# Sheet1.net
KiCad netlist of a schematic drawn in Altium Designer
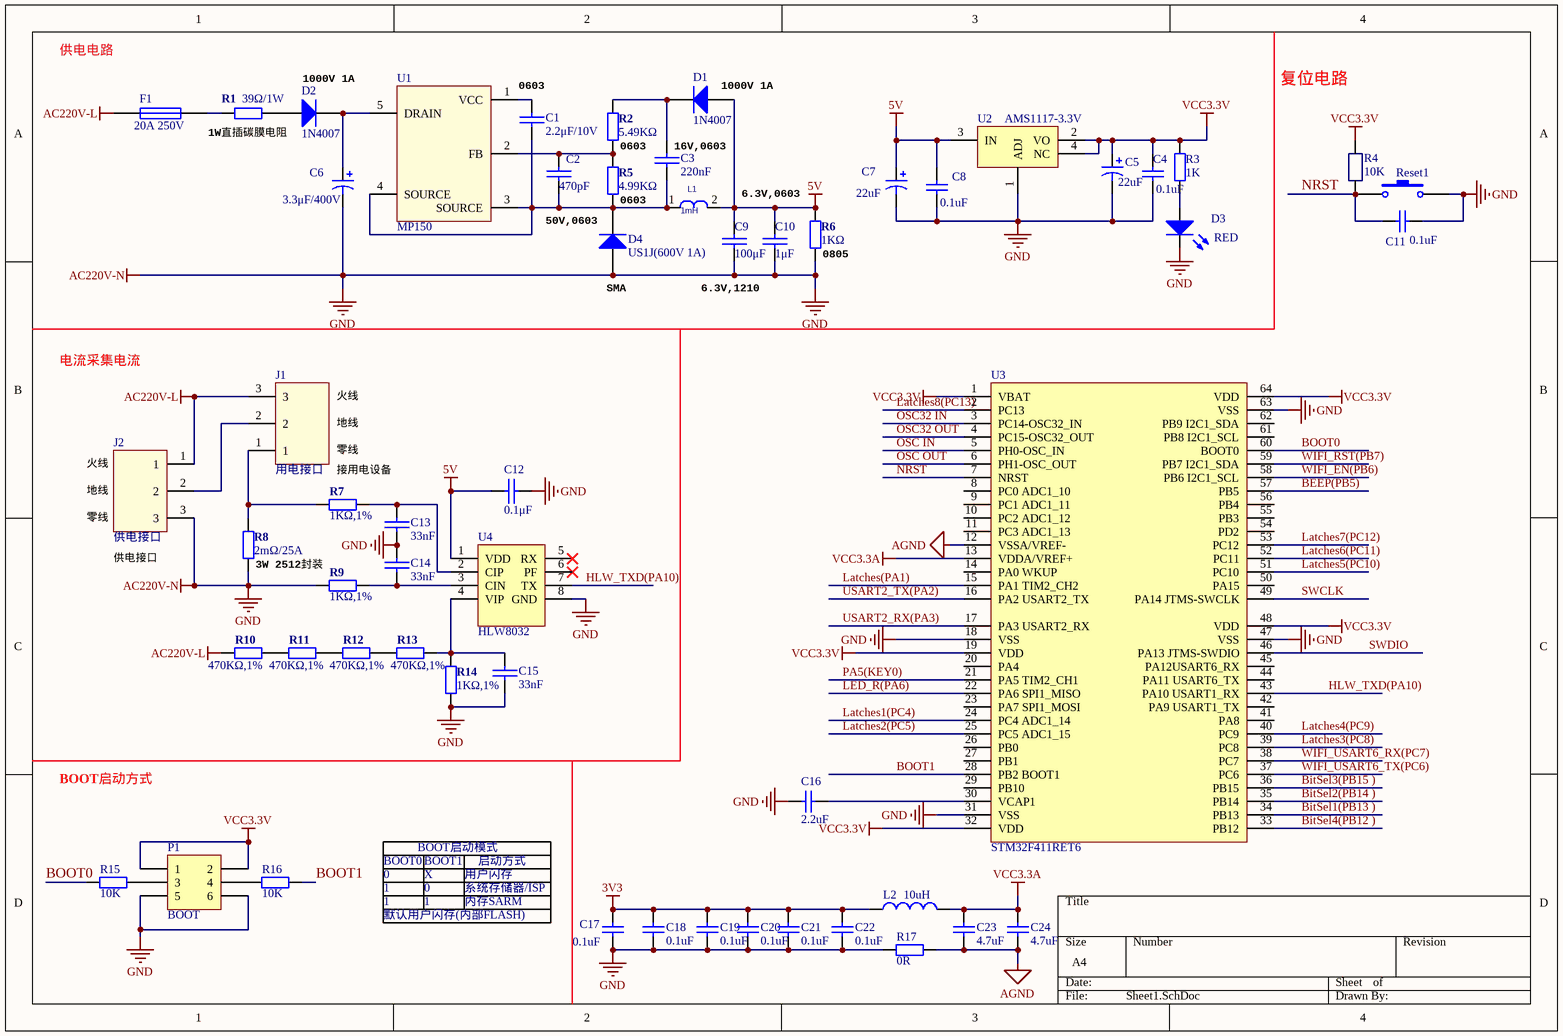
[diagram p0: Sheet1.SchDoc]

(export (version "E")
  (design (tool "Eeschema 10.0.6"))
  (components
    (comp (ref "C1")
      (value "2.2μF/10V")
      (footprint "LC-0603_C(2.2UF/10V)")
      (description "贴片电容")
      (libsource (lib "原理图库") (part "CAP"))
    )
    (comp (ref "C2")
      (value "470pF")
      (footprint "LC-0603_C(普通电容)")
      (description "贴片电容")
      (libsource (lib "原理图库") (part "CAP"))
    )
    (comp (ref "C3")
      (value "220nF")
      (footprint "LC-0603_C(普通电容)")
      (description "贴片电容")
      (libsource (lib "原理图库") (part "CAP"))
    )
    (comp (ref "C4")
      (value "0.1uF")
      (footprint "LC-0603_C(普通电容)")
      (description "贴片电容")
      (libsource (lib "Schlib1") (part "CAP"))
    )
    (comp (ref "C5")
      (value "22uF")
      (footprint "钽电容0603（25v）")
      (description "钽电容")
      (libsource (lib "Schlib1") (part "Cap Pol2"))
    )
    (comp (ref "C6")
      (value "3.3μF/400V")
      (footprint "直插电解电容 - duplicate")
      (description "直插电解电容")
      (libsource (lib "Miscellaneous Devices") (part "Cap Pol1"))
    )
    (comp (ref "C7")
      (value "22uF")
      (footprint "钽电容0603（25v）")
      (description "钽电容、")
      (libsource (lib "Schlib1") (part "Cap Pol2"))
    )
    (comp (ref "C8")
      (value "0.1uF")
      (footprint "LC-0603_C(普通电容)")
      (description "贴片电容")
      (libsource (lib "Schlib1") (part "CAP"))
    )
    (comp (ref "C9")
      (value "100μF")
      (footprint "LC-1210_C大电容")
      (description "贴片电容")
      (libsource (lib "原理图库") (part "CAP"))
    )
    (comp (ref "C10")
      (value "1μF")
      (footprint "LC-0603_C(普通电容)")
      (description "贴片电容")
      (libsource (lib "原理图库") (part "CAP"))
    )
    (comp (ref "C11")
      (value "0.1uF")
      (footprint "LC-0603_C(普通电容)")
      (description "贴片电容")
      (fields (field (name "PUBLISHER") "Altium Limited"))
      (libsource (lib "Miscellaneous Devices") (part "Cap Semi"))
    )
    (comp (ref "C12")
      (value "0.1μF")
      (footprint "LC-0603_C(普通电容)")
      (description "贴片电容")
      (libsource (lib "原理图库") (part "CAP"))
    )
    (comp (ref "C13")
      (value "33nF")
      (footprint "LC-0805_C")
      (description "贴片电容")
      (libsource (lib "原理图库") (part "CAP"))
    )
    (comp (ref "C14")
      (value "33nF")
      (footprint "LC-0805_C")
      (description "贴片电容")
      (libsource (lib "原理图库") (part "CAP"))
    )
    (comp (ref "C15")
      (value "33nF")
      (footprint "LC-0805_C")
      (description "贴片电容")
      (libsource (lib "原理图库") (part "CAP"))
    )
    (comp (ref "C16")
      (value "2.2uF")
      (footprint "PcbLib1:LC-0603_C(普通电容)")
      (description "贴片电容")
      (libsource (lib "Schlib1") (part "CAP"))
    )
    (comp (ref "C17")
      (value "0.1uF")
      (footprint "PcbLib1:LC-0603_C(普通电容)")
      (description "贴片电容")
      (libsource (lib "Schlib1") (part "CAP"))
    )
    (comp (ref "C18")
      (value "0.1uF")
      (footprint "LC-0603_C(普通电容)")
      (description "贴片电容")
      (libsource (lib "Schlib1") (part "CAP"))
    )
    (comp (ref "C19")
      (value "0.1uF")
      (footprint "PcbLib1:LC-0603_C(普通电容)")
      (description "贴片电容")
      (libsource (lib "Schlib1") (part "CAP"))
    )
    (comp (ref "C20")
      (value "0.1uF")
      (footprint "PcbLib1:LC-0603_C(普通电容)")
      (description "贴片电容")
      (libsource (lib "Schlib1") (part "CAP"))
    )
    (comp (ref "C21")
      (value "0.1uF")
      (footprint "PcbLib1:LC-0603_C(普通电容)")
      (description "贴片电容")
      (libsource (lib "Schlib1") (part "CAP"))
    )
    (comp (ref "C22")
      (value "0.1uF")
      (footprint "PcbLib1:LC-0603_C(普通电容)")
      (description "贴片电容")
      (libsource (lib "Schlib1") (part "CAP"))
    )
    (comp (ref "C23")
      (value "4.7uF")
      (footprint "PcbLib1:LC-0603_C(普通电容)")
      (description "贴片电容")
      (libsource (lib "Schlib1") (part "CAP"))
    )
    (comp (ref "C24")
      (value "4.7uF")
      (footprint "PcbLib1:LC-0603_C(普通电容)")
      (description "贴片电容")
      (libsource (lib "Schlib1") (part "CAP"))
    )
    (comp (ref "D1")
      (value "1N4007")
      (footprint "1N4007")
      (description "贴片二极管")
      (libsource (lib "Miscellaneous Devices") (part "Diode 1N5408"))
    )
    (comp (ref "D2")
      (value "1N4007")
      (footprint "1N4007")
      (description "贴片二极管")
      (libsource (lib "Miscellaneous Devices") (part "Diode 1N5408"))
    )
    (comp (ref "D3")
      (value "RED")
      (footprint "LED0603")
      (description "发光二极管0603")
      (libsource (lib "Schlib1") (part "LED1"))
    )
    (comp (ref "D4")
      (value "US1J(600V 1A)")
      (footprint "US1J二极管LC-SMA(DO-214AC)_S1")
      (description "贴片二极管")
      (fields (field (name "PUBLISHER") "Altium Limited"))
      (libsource (lib "Miscellaneous Devices") (part "Diode 1N5408"))
    )
    (comp (ref "F1")
      (value "20A 250V")
      (footprint "FUSE_BASE")
      (description "Fuse")
      (libsource (lib "Miscellaneous Devices") (part "Fuse 1"))
    )
    (comp (ref "J1")
      (value "用电接口")
      (footprint "3.81-3P(接线端子)输出")
      (description "直插接线端子")
      (libsource (lib "") (part "Port-3P_1"))
    )
    (comp (ref "J2")
      (value "供电接口")
      (footprint "3.81-3P(接线端子)输入")
      (description "直插接线端子")
      (libsource (lib "HLW8012-Demo") (part "Port-3P"))
    )
    (comp (ref "L1")
      (value "1mH")
      (footprint "L-10X14(电感)")
      (description "直插绕线电感")
      (libsource (lib "*") (part "IND_8"))
    )
    (comp (ref "L2")
      (value "10uH")
      (footprint "PcbLib1:电感(L0603)")
      (description "Inductor")
      (libsource (lib "Schlib1") (part "Inductor"))
    )
    (comp (ref "P1")
      (value "BOOT")
      (footprint "Header2*3 2.54mm")
      (description "Header, 3-Pin, 杜邦线2.54")
      (fields (field (name "PUBLISHER") "Altium Limited"))
      (libsource (lib "阿波罗STM32F4&F7底板封装库") (part "Header 3X2"))
    )
    (comp (ref "R1")
      (value "39Ω/1W")
      (footprint "炭膜电阻")
      (description "贴片电阻")
      (libsource (lib "") (part "电阻_3"))
    )
    (comp (ref "R2")
      (value "5.49KΩ")
      (footprint "LC-0603_R(电阻)")
      (description "贴片电阻")
      (libsource (lib "") (part "电阻_2"))
    )
    (comp (ref "R3")
      (value "1K")
      (footprint "LC-0603_R(电阻)")
      (description "贴片电阻")
      (fields (field (name "Comment") "10k") (field (name "PUBLISHER") "Altium Limited"))
      (libsource (lib "Miscellaneous Devices") (part "Res2"))
    )
    (comp (ref "R4")
      (value "10K")
      (footprint "LC-0603_R(电阻)")
      (description "贴片电阻")
      (libsource (lib "PCB") (part "RES"))
    )
    (comp (ref "R5")
      (value "4.99KΩ")
      (footprint "LC-0603_R(电阻)")
      (description "贴片电阻")
      (libsource (lib "") (part "电阻_2"))
    )
    (comp (ref "R6")
      (value "1KΩ")
      (footprint "LC-0805_R")
      (description "贴片电阻")
      (libsource (lib "") (part "电阻_2"))
    )
    (comp (ref "R7")
      (value "1KΩ,1%")
      (footprint "LC-0805_R")
      (description "贴片电阻")
      (libsource (lib "") (part "电阻_1"))
    )
    (comp (ref "R8")
      (value "2mΩ/25A")
      (footprint "R2512猛铜电阻")
      (description "贴片电阻")
      (libsource (lib "FourAxis") (part "电阻"))
    )
    (comp (ref "R9")
      (value "1KΩ,1%")
      (footprint "LC-0805_R")
      (description "贴片电阻")
      (libsource (lib "") (part "电阻_1"))
    )
    (comp (ref "R10")
      (value "470KΩ,1%")
      (footprint "LC-0805_R")
      (description "贴片电阻")
      (libsource (lib "") (part "电阻_1"))
    )
    (comp (ref "R11")
      (value "470KΩ,1%")
      (footprint "LC-0805_R")
      (description "贴片电阻")
      (libsource (lib "") (part "电阻_1"))
    )
    (comp (ref "R12")
      (value "470KΩ,1%")
      (footprint "LC-0805_R")
      (description "贴片电阻")
      (libsource (lib "") (part "电阻_1"))
    )
    (comp (ref "R13")
      (value "470KΩ,1%")
      (footprint "LC-0805_R")
      (description "贴片电阻")
      (libsource (lib "") (part "电阻_1"))
    )
    (comp (ref "R14")
      (value "1KΩ,1%")
      (footprint "LC-0805_R")
      (description "贴片电阻")
      (libsource (lib "FourAxis") (part "电阻"))
    )
    (comp (ref "R15")
      (value "10K")
      (footprint "LC-0603_R(电阻)")
      (description "贴片电阻")
      (fields (field (name "Comment") "10k") (field (name "PUBLISHER") "Altium Limited"))
      (libsource (lib "") (part "Res2_1"))
    )
    (comp (ref "R16")
      (value "10K")
      (footprint "LC-0603_R(电阻)")
      (description "贴片电阻")
      (fields (field (name "Comment") "10k") (field (name "PUBLISHER") "Altium Limited"))
      (libsource (lib "") (part "Res2_1"))
    )
    (comp (ref "R17")
      (value "0R")
      (footprint "LC-0603_R(电阻)")
      (description "贴片电阻")
      (fields (field (name "Comment") "10k") (field (name "PUBLISHER") "Altium Limited"))
      (libsource (lib "") (part "Res2_1"))
    )
    (comp (ref "Reset1")
      (value "SW-PB")
      (footprint "key")
      (description "轻触开关 3*6*2.5mm 白头")
      (fields (field (name "PUBLISHER") "Altium Limited"))
      (libsource (lib "Miscellaneous Devices") (part "SW-PB"))
    )
    (comp (ref "U1")
      (value "MP150")
      (footprint "MP150(LC-SOT-23-5)")
      (description "IC")
      (libsource (lib "HLW8012-Demo") (part "MP150"))
    )
    (comp (ref "U2")
      (value "AMS1117-3.3V")
      (footprint "SOT-223(ASM117-3.3)")
      (description "稳压芯片转3V3")
      (libsource (lib "Schlib1") (part "AMS1117-3.3V"))
    )
    (comp (ref "U3")
      (value "STM32F411RET6")
      (footprint "MCU-LQFP64")
      (description "MCU")
      (libsource (lib "Schlib1") (part "STM32F411"))
    )
    (comp (ref "U4")
      (value "HLW8032")
      (footprint "(HLW8032)LC-SOP-8_150mil")
      (description "电量计芯片")
      (libsource (lib "Schlib1") (part "HLW8032"))
    )
  )
  (nets
    (net (code "1") (name "/BEEP(PB5)") (class "Default")
      (node (ref "U3") (pin "57") (pinfunction "PB5_57") (pintype "passive"))
    )
    (net (code "2") (name "/BOOT0") (class "Default")
      (node (ref "R15") (pin "2") (pinfunction "2_2") (pintype "passive"))
      (node (ref "U3") (pin "60") (pinfunction "BOOT0_60") (pintype "passive"))
    )
    (net (code "3") (name "/BOOT1") (class "Default")
      (node (ref "R16") (pin "1") (pinfunction "1_1") (pintype "passive"))
      (node (ref "U3") (pin "28") (pinfunction "PB2_BOOT1_28") (pintype "passive"))
    )
    (net (code "4") (name "/BitSel1(PB13 )") (class "Default")
      (node (ref "U3") (pin "34") (pinfunction "PB13_34") (pintype "passive"))
    )
    (net (code "5") (name "/BitSel2(PB14 )") (class "Default")
      (node (ref "U3") (pin "35") (pinfunction "PB14_35") (pintype "passive"))
    )
    (net (code "6") (name "/BitSel3(PB15 )") (class "Default")
      (node (ref "U3") (pin "36") (pinfunction "PB15_36") (pintype "passive"))
    )
    (net (code "7") (name "/BitSel4(PB12 )") (class "Default")
      (node (ref "U3") (pin "33") (pinfunction "PB12_33") (pintype "passive"))
    )
    (net (code "8") (name "/HLW_TXD(PA10)") (class "Default")
      (node (ref "U3") (pin "43") (pinfunction "PA10_USART1_RX_43") (pintype "passive"))
      (node (ref "U4") (pin "7") (pinfunction "TX_7") (pintype "passive"))
    )
    (net (code "9") (name "/LED_R(PA6)") (class "Default")
      (node (ref "U3") (pin "22") (pinfunction "PA6_SPI1_MISO_22") (pintype "passive"))
    )
    (net (code "10") (name "/Latches(PA1)") (class "Default")
      (node (ref "U3") (pin "15") (pinfunction "PA1_TIM2_CH2_15") (pintype "passive"))
    )
    (net (code "11") (name "/Latches1(PC4)") (class "Default")
      (node (ref "U3") (pin "24") (pinfunction "PC4_ADC1_14_24") (pintype "passive"))
    )
    (net (code "12") (name "/Latches2(PC5)") (class "Default")
      (node (ref "U3") (pin "25") (pinfunction "PC5_ADC1_15_25") (pintype "passive"))
    )
    (net (code "13") (name "/Latches3(PC8)") (class "Default")
      (node (ref "U3") (pin "39") (pinfunction "PC8_39") (pintype "passive"))
    )
    (net (code "14") (name "/Latches4(PC9)") (class "Default")
      (node (ref "U3") (pin "40") (pinfunction "PC9_40") (pintype "passive"))
    )
    (net (code "15") (name "/Latches5(PC10)") (class "Default")
      (node (ref "U3") (pin "51") (pinfunction "PC10_51") (pintype "passive"))
    )
    (net (code "16") (name "/Latches6(PC11)") (class "Default")
      (node (ref "U3") (pin "52") (pinfunction "PC11_52") (pintype "passive"))
    )
    (net (code "17") (name "/Latches7(PC12)") (class "Default")
      (node (ref "U3") (pin "53") (pinfunction "PC12_53") (pintype "passive"))
    )
    (net (code "18") (name "/Latches8(PC13)") (class "Default")
      (node (ref "U3") (pin "2") (pinfunction "PC13_2") (pintype "passive"))
    )
    (net (code "19") (name "/NRST") (class "Default")
      (node (ref "C11") (pin "2") (pinfunction "2_2") (pintype "passive"))
      (node (ref "R4") (pin "1") (pinfunction "1_1") (pintype "passive"))
      (node (ref "Reset1") (pin "1") (pinfunction "1_1") (pintype "passive"))
      (node (ref "U3") (pin "7") (pinfunction "NRST_7") (pintype "passive"))
    )
    (net (code "20") (name "/OSC IN") (class "Default")
      (node (ref "U3") (pin "5") (pinfunction "PH0-OSC_IN_5") (pintype "passive"))
    )
    (net (code "21") (name "/OSC OUT") (class "Default")
      (node (ref "U3") (pin "6") (pinfunction "PH1-OSC_OUT_6") (pintype "passive"))
    )
    (net (code "22") (name "/OSC32 IN") (class "Default")
      (node (ref "U3") (pin "3") (pinfunction "PC14-OSC32_IN_3") (pintype "passive"))
    )
    (net (code "23") (name "/OSC32 OUT") (class "Default")
      (node (ref "U3") (pin "4") (pinfunction "PC15-OSC32_OUT_4") (pintype "passive"))
    )
    (net (code "24") (name "/PA5(KEY0)") (class "Default")
      (node (ref "U3") (pin "21") (pinfunction "PA5_TIM2_CH1_21") (pintype "passive"))
    )
    (net (code "25") (name "/SWCLK") (class "Default")
      (node (ref "U3") (pin "49") (pinfunction "PA14_JTMS-SWCLK_49") (pintype "passive"))
    )
    (net (code "26") (name "/SWDIO") (class "Default")
      (node (ref "U3") (pin "46") (pinfunction "PA13_JTMS-SWDIO_46") (pintype "passive"))
    )
    (net (code "27") (name "/USART2_RX(PA3)") (class "Default")
      (node (ref "U3") (pin "17") (pinfunction "PA3_USART2_RX_17") (pintype "passive"))
    )
    (net (code "28") (name "/USART2_TX(PA2)") (class "Default")
      (node (ref "U3") (pin "16") (pinfunction "PA2_USART2_TX_16") (pintype "passive"))
    )
    (net (code "29") (name "/WIFI_EN(PB6)") (class "Default")
      (node (ref "U3") (pin "58") (pinfunction "PB6_I2C1_SCL_58") (pintype "passive"))
    )
    (net (code "30") (name "/WIFI_RST(PB7)") (class "Default")
      (node (ref "U3") (pin "59") (pinfunction "PB7_I2C1_SDA_59") (pintype "passive"))
    )
    (net (code "31") (name "/WIFI_USART6_RX(PC7)") (class "Default")
      (node (ref "U3") (pin "38") (pinfunction "PC7_38") (pintype "passive"))
    )
    (net (code "32") (name "/WIFI_USART6_TX(PC6)") (class "Default")
      (node (ref "U3") (pin "37") (pinfunction "PC6_37") (pintype "passive"))
    )
    (net (code "33") (name "3V3") (class "Default")
      (node (ref "C17") (pin "2") (pinfunction "2_2") (pintype "passive"))
      (node (ref "C18") (pin "2") (pinfunction "2_2") (pintype "passive"))
      (node (ref "C19") (pin "2") (pinfunction "2_2") (pintype "passive"))
      (node (ref "C20") (pin "1") (pinfunction "1_1") (pintype "passive"))
      (node (ref "C21") (pin "1") (pinfunction "1_1") (pintype "passive"))
      (node (ref "C22") (pin "1") (pinfunction "1_1") (pintype "passive"))
      (node (ref "L2") (pin "1") (pinfunction "1_1") (pintype "passive"))
    )
    (net (code "34") (name "5V") (class "Default")
      (node (ref "C10") (pin "2") (pinfunction "2_2") (pintype "passive"))
      (node (ref "C12") (pin "1") (pinfunction "1_1") (pintype "passive"))
      (node (ref "C7") (pin "1") (pinfunction "1_1") (pintype "passive"))
      (node (ref "C8") (pin "2") (pinfunction "2_2") (pintype "passive"))
      (node (ref "C9") (pin "2") (pinfunction "2_2") (pintype "passive"))
      (node (ref "D1") (pin "1") (pinfunction "A_1") (pintype "passive"))
      (node (ref "L1") (pin "2") (pinfunction "2_2") (pintype "passive"))
      (node (ref "R6") (pin "2") (pinfunction "2_2") (pintype "passive"))
      (node (ref "U2") (pin "3") (pinfunction "IN_3") (pintype "passive"))
      (node (ref "U4") (pin "1") (pinfunction "VDD_1") (pintype "passive"))
    )
    (net (code "35") (name "AC220V-L") (class "Default")
      (node (ref "F1") (pin "2") (pinfunction "2_2") (pintype "passive"))
      (node (ref "J1") (pin "3") (pinfunction "3_3") (pintype "passive"))
      (node (ref "J2") (pin "1") (pinfunction "1_1") (pintype "passive"))
      (node (ref "R10") (pin "2") (pinfunction "2_2") (pintype "passive"))
    )
    (net (code "36") (name "AC220V-N") (class "Default")
      (node (ref "C10") (pin "1") (pinfunction "1_1") (pintype "passive"))
      (node (ref "C11") (pin "1") (pinfunction "1_1") (pintype "passive"))
      (node (ref "C12") (pin "2") (pinfunction "2_2") (pintype "passive"))
      (node (ref "C13") (pin "2") (pinfunction "2_2") (pintype "passive"))
      (node (ref "C14") (pin "1") (pinfunction "1_1") (pintype "passive"))
      (node (ref "C15") (pin "2") (pinfunction "2_2") (pintype "passive"))
      (node (ref "C16") (pin "1") (pinfunction "1_1") (pintype "passive"))
      (node (ref "C17") (pin "1") (pinfunction "1_1") (pintype "passive"))
      (node (ref "C18") (pin "1") (pinfunction "1_1") (pintype "passive"))
      (node (ref "C19") (pin "1") (pinfunction "1_1") (pintype "passive"))
      (node (ref "C20") (pin "2") (pinfunction "2_2") (pintype "passive"))
      (node (ref "C21") (pin "2") (pinfunction "2_2") (pintype "passive"))
      (node (ref "C22") (pin "2") (pinfunction "2_2") (pintype "passive"))
      (node (ref "C4") (pin "1") (pinfunction "1_1") (pintype "passive"))
      (node (ref "C5") (pin "2") (pinfunction "2_2") (pintype "passive"))
      (node (ref "C6") (pin "2") (pinfunction "2_2") (pintype "passive"))
      (node (ref "C7") (pin "2") (pinfunction "2_2") (pintype "passive"))
      (node (ref "C8") (pin "1") (pinfunction "1_1") (pintype "passive"))
      (node (ref "C9") (pin "1") (pinfunction "1_1") (pintype "passive"))
      (node (ref "D3") (pin "2") (pinfunction "K_2") (pintype "passive"))
      (node (ref "D4") (pin "1") (pinfunction "A_1") (pintype "passive"))
      (node (ref "J2") (pin "3") (pinfunction "3_3") (pintype "passive"))
      (node (ref "P1") (pin "5") (pinfunction "5_5") (pintype "passive"))
      (node (ref "P1") (pin "6") (pinfunction "6_6") (pintype "passive"))
      (node (ref "R14") (pin "2") (pinfunction "2_2") (pintype "passive"))
      (node (ref "R17") (pin "2") (pinfunction "2_2") (pintype "passive"))
      (node (ref "R6") (pin "1") (pinfunction "1_1") (pintype "passive"))
      (node (ref "R8") (pin "2") (pinfunction "2_2") (pintype "passive"))
      (node (ref "R9") (pin "2") (pinfunction "2_2") (pintype "passive"))
      (node (ref "Reset1") (pin "2") (pinfunction "2_2") (pintype "passive"))
      (node (ref "U2") (pin "1") (pinfunction "ADJ_1") (pintype "passive"))
      (node (ref "U3") (pin "18") (pinfunction "VSS_18") (pintype "passive"))
      (node (ref "U3") (pin "31") (pinfunction "VSS_31") (pintype "passive"))
      (node (ref "U3") (pin "47") (pinfunction "VSS_47") (pintype "passive"))
      (node (ref "U3") (pin "63") (pinfunction "VSS_63") (pintype "passive"))
      (node (ref "U4") (pin "8") (pinfunction "GND_8") (pintype "passive"))
    )
    (net (code "37") (name "AGND") (class "Default")
      (node (ref "C23") (pin "1") (pinfunction "1_1") (pintype "passive"))
      (node (ref "C24") (pin "1") (pinfunction "1_1") (pintype "passive"))
      (node (ref "R17") (pin "1") (pinfunction "1_1") (pintype "passive"))
      (node (ref "U3") (pin "12") (pinfunction "VSSA/VREF-_12") (pintype "passive"))
    )
    (net (code "38") (name "Net-(D1-K)") (class "Default")
      (node (ref "C3") (pin "2") (pinfunction "2_2") (pintype "passive"))
      (node (ref "D1") (pin "2") (pinfunction "K_2") (pintype "passive"))
      (node (ref "R2") (pin "2") (pinfunction "2_2") (pintype "passive"))
    )
    (net (code "39") (name "Net-(D2-A)") (class "Default")
      (node (ref "D2") (pin "1") (pinfunction "A_1") (pintype "passive"))
      (node (ref "R1") (pin "2") (pinfunction "2_2") (pintype "passive"))
    )
    (net (code "40") (name "Net-(D2-K)") (class "Default")
      (node (ref "C6") (pin "1") (pinfunction "1_1") (pintype "passive"))
      (node (ref "D2") (pin "2") (pinfunction "K_2") (pintype "passive"))
      (node (ref "U1") (pin "5") (pinfunction "DRAIN_5") (pintype "passive"))
    )
    (net (code "41") (name "Net-(D3-A)") (class "Default")
      (node (ref "D3") (pin "1") (pinfunction "A_1") (pintype "passive"))
      (node (ref "R3") (pin "2") (pinfunction "2_2") (pintype "passive"))
    )
    (net (code "42") (name "Net-(D4-K)") (class "Default")
      (node (ref "C1") (pin "1") (pinfunction "1_1") (pintype "passive"))
      (node (ref "C2") (pin "1") (pinfunction "1_1") (pintype "passive"))
      (node (ref "C3") (pin "1") (pinfunction "1_1") (pintype "passive"))
      (node (ref "D4") (pin "2") (pinfunction "K_2") (pintype "passive"))
      (node (ref "L1") (pin "1") (pinfunction "1_1") (pintype "passive"))
      (node (ref "R5") (pin "1") (pinfunction "1_1") (pintype "passive"))
      (node (ref "U1") (pin "3") (pinfunction "SOURCE_3") (pintype "passive"))
      (node (ref "U1") (pin "4") (pinfunction "SOURCE_4") (pintype "passive"))
    )
    (net (code "43") (name "Net-(F1-Pad1)") (class "Default")
      (node (ref "F1") (pin "1") (pinfunction "1_1") (pintype "passive"))
      (node (ref "R1") (pin "1") (pinfunction "1_1") (pintype "passive"))
    )
    (net (code "44") (name "Net-(J1-Pad1)") (class "Default")
      (node (ref "J1") (pin "1") (pinfunction "1_1") (pintype "passive"))
      (node (ref "R7") (pin "2") (pinfunction "2_2") (pintype "passive"))
      (node (ref "R8") (pin "1") (pinfunction "1_1") (pintype "passive"))
    )
    (net (code "45") (name "Net-(J1-Pad2)") (class "Default")
      (node (ref "J1") (pin "2") (pinfunction "2_2") (pintype "passive"))
      (node (ref "J2") (pin "2") (pinfunction "2_2") (pintype "passive"))
    )
    (net (code "46") (name "Net-(P1-Pad3)") (class "Default")
      (node (ref "P1") (pin "3") (pinfunction "3_3") (pintype "passive"))
      (node (ref "R15") (pin "1") (pinfunction "1_1") (pintype "passive"))
    )
    (net (code "47") (name "Net-(P1-Pad4)") (class "Default")
      (node (ref "P1") (pin "4") (pinfunction "4_4") (pintype "passive"))
      (node (ref "R16") (pin "2") (pinfunction "2_2") (pintype "passive"))
    )
    (net (code "48") (name "Net-(R10-Pad1)") (class "Default")
      (node (ref "R10") (pin "1") (pinfunction "1_1") (pintype "passive"))
      (node (ref "R11") (pin "2") (pinfunction "2_2") (pintype "passive"))
    )
    (net (code "49") (name "Net-(R11-Pad1)") (class "Default")
      (node (ref "R11") (pin "1") (pinfunction "1_1") (pintype "passive"))
      (node (ref "R12") (pin "2") (pinfunction "2_2") (pintype "passive"))
    )
    (net (code "50") (name "Net-(R12-Pad1)") (class "Default")
      (node (ref "R12") (pin "1") (pinfunction "1_1") (pintype "passive"))
      (node (ref "R13") (pin "2") (pinfunction "2_2") (pintype "passive"))
    )
    (net (code "51") (name "Net-(U1-FB)") (class "Default")
      (node (ref "C2") (pin "2") (pinfunction "2_2") (pintype "passive"))
      (node (ref "R2") (pin "1") (pinfunction "1_1") (pintype "passive"))
      (node (ref "R5") (pin "2") (pinfunction "2_2") (pintype "passive"))
      (node (ref "U1") (pin "2") (pinfunction "FB_2") (pintype "passive"))
    )
    (net (code "52") (name "Net-(U1-VCC)") (class "Default")
      (node (ref "C1") (pin "2") (pinfunction "2_2") (pintype "passive"))
      (node (ref "U1") (pin "1") (pinfunction "VCC_1") (pintype "passive"))
    )
    (net (code "53") (name "Net-(U3-VCAP1)") (class "Default")
      (node (ref "C16") (pin "2") (pinfunction "2_2") (pintype "passive"))
      (node (ref "U3") (pin "30") (pinfunction "VCAP1_30") (pintype "passive"))
    )
    (net (code "54") (name "Net-(U4-CIN)") (class "Default")
      (node (ref "C14") (pin "2") (pinfunction "2_2") (pintype "passive"))
      (node (ref "R9") (pin "1") (pinfunction "1_1") (pintype "passive"))
      (node (ref "U4") (pin "3") (pinfunction "CIN_3") (pintype "passive"))
    )
    (net (code "55") (name "Net-(U4-CIP)") (class "Default")
      (node (ref "C13") (pin "1") (pinfunction "1_1") (pintype "passive"))
      (node (ref "R7") (pin "1") (pinfunction "1_1") (pintype "passive"))
      (node (ref "U4") (pin "2") (pinfunction "CIP_2") (pintype "passive"))
    )
    (net (code "56") (name "Net-(U4-VIP)") (class "Default")
      (node (ref "C15") (pin "1") (pinfunction "1_1") (pintype "passive"))
      (node (ref "R13") (pin "1") (pinfunction "1_1") (pintype "passive"))
      (node (ref "R14") (pin "1") (pinfunction "1_1") (pintype "passive"))
      (node (ref "U4") (pin "4") (pinfunction "VIP_4") (pintype "passive"))
    )
    (net (code "57") (name "VCC3.3A") (class "Default")
      (node (ref "C23") (pin "2") (pinfunction "2_2") (pintype "passive"))
      (node (ref "C24") (pin "2") (pinfunction "2_2") (pintype "passive"))
      (node (ref "L2") (pin "2") (pinfunction "2_2") (pintype "passive"))
      (node (ref "U3") (pin "13") (pinfunction "VDDA/VREF+_13") (pintype "passive"))
    )
    (net (code "58") (name "VCC3.3V") (class "Default")
      (node (ref "C4") (pin "2") (pinfunction "2_2") (pintype "passive"))
      (node (ref "C5") (pin "1") (pinfunction "1_1") (pintype "passive"))
      (node (ref "P1") (pin "1") (pinfunction "1_1") (pintype "passive"))
      (node (ref "P1") (pin "2") (pinfunction "2_2") (pintype "passive"))
      (node (ref "R3") (pin "1") (pinfunction "1_1") (pintype "passive"))
      (node (ref "R4") (pin "2") (pinfunction "2_2") (pintype "passive"))
      (node (ref "U2") (pin "2") (pinfunction "VO_2") (pintype "passive"))
      (node (ref "U2") (pin "4") (pinfunction "NC_4") (pintype "passive"))
      (node (ref "U3") (pin "1") (pinfunction "VBAT_1") (pintype "passive"))
      (node (ref "U3") (pin "19") (pinfunction "VDD_19") (pintype "passive"))
      (node (ref "U3") (pin "32") (pinfunction "VDD_32") (pintype "passive"))
      (node (ref "U3") (pin "48") (pinfunction "VDD_48") (pintype "passive"))
      (node (ref "U3") (pin "64") (pinfunction "VDD_64") (pintype "passive"))
    )
    (net (code "59") (name "unconnected-(U3-PA0_WKUP-Pad14)") (class "Default")
      (node (ref "U3") (pin "14") (pinfunction "PA0_WKUP_14") (pintype "passive"))
    )
    (net (code "60") (name "unconnected-(U3-PA4-Pad20)") (class "Default")
      (node (ref "U3") (pin "20") (pinfunction "PA4_20") (pintype "passive"))
    )
    (net (code "61") (name "unconnected-(U3-PA7_SPI1_MOSI-Pad23)") (class "Default")
      (node (ref "U3") (pin "23") (pinfunction "PA7_SPI1_MOSI_23") (pintype "passive"))
    )
    (net (code "62") (name "unconnected-(U3-PA8-Pad41)") (class "Default")
      (node (ref "U3") (pin "41") (pinfunction "PA8_41") (pintype "passive"))
    )
    (net (code "63") (name "unconnected-(U3-PA9_USART1_TX-Pad42)") (class "Default")
      (node (ref "U3") (pin "42") (pinfunction "PA9_USART1_TX_42") (pintype "passive"))
    )
    (net (code "64") (name "unconnected-(U3-PA11_USART6_TX-Pad44)") (class "Default")
      (node (ref "U3") (pin "44") (pinfunction "PA11_USART6_TX_44") (pintype "passive"))
    )
    (net (code "65") (name "unconnected-(U3-PA12USART6_RX-Pad45)") (class "Default")
      (node (ref "U3") (pin "45") (pinfunction "PA12USART6_RX_45") (pintype "passive"))
    )
    (net (code "66") (name "unconnected-(U3-PA15-Pad50)") (class "Default")
      (node (ref "U3") (pin "50") (pinfunction "PA15_50") (pintype "passive"))
    )
    (net (code "67") (name "unconnected-(U3-PB0-Pad26)") (class "Default")
      (node (ref "U3") (pin "26") (pinfunction "PB0_26") (pintype "passive"))
    )
    (net (code "68") (name "unconnected-(U3-PB1-Pad27)") (class "Default")
      (node (ref "U3") (pin "27") (pinfunction "PB1_27") (pintype "passive"))
    )
    (net (code "69") (name "unconnected-(U3-PB3-Pad55)") (class "Default")
      (node (ref "U3") (pin "55") (pinfunction "PB3_55") (pintype "passive"))
    )
    (net (code "70") (name "unconnected-(U3-PB4-Pad56)") (class "Default")
      (node (ref "U3") (pin "56") (pinfunction "PB4_56") (pintype "passive"))
    )
    (net (code "71") (name "unconnected-(U3-PB8_I2C1_SCL-Pad61)") (class "Default")
      (node (ref "U3") (pin "61") (pinfunction "PB8_I2C1_SCL_61") (pintype "passive"))
    )
    (net (code "72") (name "unconnected-(U3-PB9_I2C1_SDA-Pad62)") (class "Default")
      (node (ref "U3") (pin "62") (pinfunction "PB9_I2C1_SDA_62") (pintype "passive"))
    )
    (net (code "73") (name "unconnected-(U3-PB10-Pad29)") (class "Default")
      (node (ref "U3") (pin "29") (pinfunction "PB10_29") (pintype "passive"))
    )
    (net (code "74") (name "unconnected-(U3-PC0_ADC1_10-Pad8)") (class "Default")
      (node (ref "U3") (pin "8") (pinfunction "PC0_ADC1_10_8") (pintype "passive"))
    )
    (net (code "75") (name "unconnected-(U3-PC1_ADC1_11-Pad9)") (class "Default")
      (node (ref "U3") (pin "9") (pinfunction "PC1_ADC1_11_9") (pintype "passive"))
    )
    (net (code "76") (name "unconnected-(U3-PC2_ADC1_12-Pad10)") (class "Default")
      (node (ref "U3") (pin "10") (pinfunction "PC2_ADC1_12_10") (pintype "passive"))
    )
    (net (code "77") (name "unconnected-(U3-PC3_ADC1_13-Pad11)") (class "Default")
      (node (ref "U3") (pin "11") (pinfunction "PC3_ADC1_13_11") (pintype "passive"))
    )
    (net (code "78") (name "unconnected-(U3-PD2-Pad54)") (class "Default")
      (node (ref "U3") (pin "54") (pinfunction "PD2_54") (pintype "passive"))
    )
    (net (code "79") (name "unconnected-(U4-PF-Pad6)") (class "Default")
      (node (ref "U4") (pin "6") (pinfunction "PF_6") (pintype "passive+no_connect"))
    )
    (net (code "80") (name "unconnected-(U4-RX-Pad5)") (class "Default")
      (node (ref "U4") (pin "5") (pinfunction "RX_5") (pintype "passive+no_connect"))
    )
  )
)
